# hello-ftdi-44.net
KiCad netlist of a schematic drawn in EAGLE
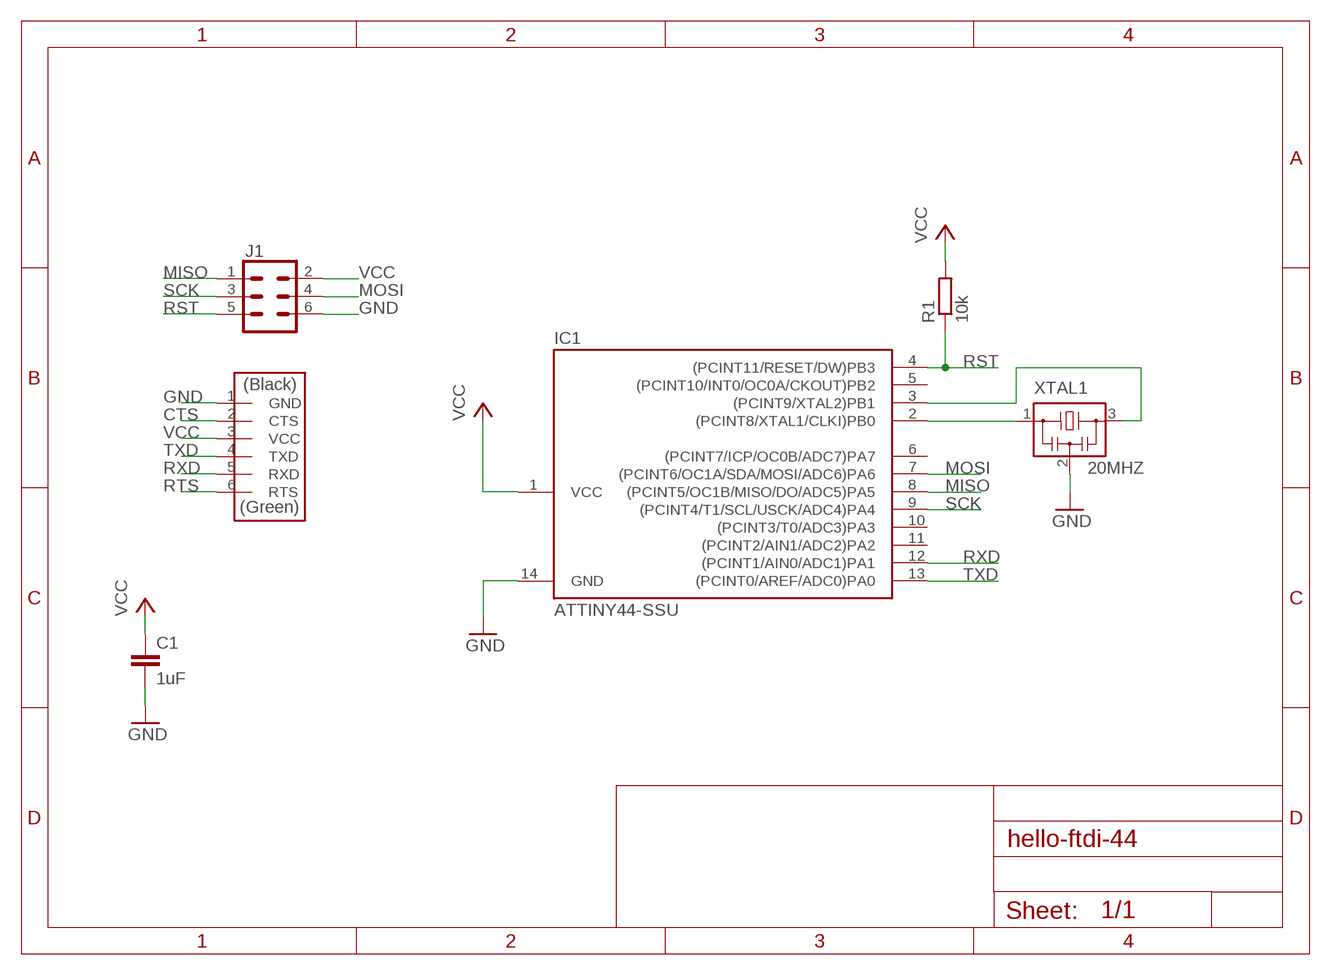
[diagram p0: schematic, sheet 1]

(export (version "E")
  (design (tool "Eeschema 10.0.6"))
  (components
    (comp (ref "C1")
      (value "1uF")
      (footprint "eagle-import:C1206")
      (libsource (lib "eagle-import") (part "C-EUC1206"))
    )
    (comp (ref "IC1")
      (value "ATTINY44-SSU")
      (footprint "eagle-import:SOIC14")
      (libsource (lib "eagle-import") (part "ATTINY44-SSU"))
    )
    (comp (ref "J1")
      (value "CONN_03X2SMT")
      (footprint "eagle-import:2X3_SMT_POSTS")
      (libsource (lib "eagle-import") (part "CONN_03X2SMT"))
    )
    (comp (ref "J2")
      (value "FTDI-SMD-HEADER")
      (footprint "eagle-import:1X06SMD")
      (libsource (lib "eagle-import") (part "FTDI-SMD-HEADER"))
    )
    (comp (ref "R1")
      (value "10k")
      (footprint "eagle-import:M1206")
      (libsource (lib "eagle-import") (part "R-EU_M1206"))
    )
    (comp (ref "XTAL1")
      (value "20MHZ")
      (footprint "eagle-import:EFOBM")
      (libsource (lib "eagle-import") (part "RESONATOR"))
    )
  )
  (nets
    (net (code "1") (name "/CTS") (class "Default")
      (node (ref "J2") (pin "2") (pinfunction "CTS_2") (pintype "bidirectional"))
    )
    (net (code "2") (name "/MISO") (class "Default")
      (node (ref "IC1") (pin "8") (pinfunction "(PCINT5/OC1B/MISO/DO/ADC5)PA5_8") (pintype "bidirectional"))
      (node (ref "J1") (pin "1") (pinfunction "1_1") (pintype "bidirectional"))
    )
    (net (code "3") (name "/MOSI") (class "Default")
      (node (ref "IC1") (pin "7") (pinfunction "(PCINT6/OC1A/SDA/MOSI/ADC6)PA6_7") (pintype "bidirectional"))
      (node (ref "J1") (pin "4") (pinfunction "4_4") (pintype "bidirectional"))
    )
    (net (code "4") (name "/RST") (class "Default")
      (node (ref "IC1") (pin "4") (pinfunction "(PCINT11/RESET/DW)PB3_4") (pintype "bidirectional"))
      (node (ref "J1") (pin "5") (pinfunction "5_5") (pintype "bidirectional"))
      (node (ref "R1") (pin "1") (pinfunction "1_1") (pintype "passive"))
    )
    (net (code "5") (name "/RTS") (class "Default")
      (node (ref "J2") (pin "6") (pinfunction "RTS_6") (pintype "bidirectional"))
    )
    (net (code "6") (name "/RXD") (class "Default")
      (node (ref "IC1") (pin "12") (pinfunction "(PCINT1/AIN0/ADC1)PA1_12") (pintype "bidirectional"))
      (node (ref "J2") (pin "5") (pinfunction "RXD_5") (pintype "bidirectional"))
    )
    (net (code "7") (name "/SCK") (class "Default")
      (node (ref "IC1") (pin "9") (pinfunction "(PCINT4/T1/SCL/USCK/ADC4)PA4_9") (pintype "bidirectional"))
      (node (ref "J1") (pin "3") (pinfunction "3_3") (pintype "bidirectional"))
    )
    (net (code "8") (name "/TXD") (class "Default")
      (node (ref "IC1") (pin "13") (pinfunction "(PCINT0/AREF/ADC0)PA0_13") (pintype "bidirectional"))
      (node (ref "J2") (pin "4") (pinfunction "TXD_4") (pintype "bidirectional"))
    )
    (net (code "9") (name "GND") (class "Default")
      (node (ref "C1") (pin "2") (pinfunction "2_2") (pintype "passive"))
      (node (ref "IC1") (pin "14") (pinfunction "GND_14") (pintype "power_in"))
      (node (ref "J1") (pin "6") (pinfunction "6_6") (pintype "bidirectional"))
      (node (ref "J2") (pin "1") (pinfunction "GND_1") (pintype "bidirectional"))
      (node (ref "XTAL1") (pin "2") (pinfunction "2_2") (pintype "passive"))
    )
    (net (code "10") (name "Net-(IC1-(PCINT8{slash}XTAL1{slash}CLKI)PB0)") (class "Default")
      (node (ref "IC1") (pin "2") (pinfunction "(PCINT8/XTAL1/CLKI)PB0_2") (pintype "bidirectional"))
      (node (ref "XTAL1") (pin "1") (pinfunction "1_1") (pintype "passive"))
    )
    (net (code "11") (name "Net-(IC1-(PCINT9{slash}XTAL2)PB1)") (class "Default")
      (node (ref "IC1") (pin "3") (pinfunction "(PCINT9/XTAL2)PB1_3") (pintype "bidirectional"))
      (node (ref "XTAL1") (pin "3") (pinfunction "3_3") (pintype "passive"))
    )
    (net (code "12") (name "VCC") (class "Default")
      (node (ref "C1") (pin "1") (pinfunction "1_1") (pintype "passive"))
      (node (ref "IC1") (pin "1") (pinfunction "VCC_1") (pintype "power_in"))
      (node (ref "J1") (pin "2") (pinfunction "2_2") (pintype "bidirectional"))
      (node (ref "J2") (pin "3") (pinfunction "VCC_3") (pintype "bidirectional"))
      (node (ref "R1") (pin "2") (pinfunction "2_2") (pintype "passive"))
    )
    (net (code "13") (name "unconnected-(IC1-(PCINT2{slash}AIN1{slash}ADC2)PA2-Pad11)") (class "Default")
      (node (ref "IC1") (pin "11") (pinfunction "(PCINT2/AIN1/ADC2)PA2_11") (pintype "bidirectional"))
    )
    (net (code "14") (name "unconnected-(IC1-(PCINT3{slash}T0{slash}ADC3)PA3-Pad10)") (class "Default")
      (node (ref "IC1") (pin "10") (pinfunction "(PCINT3/T0/ADC3)PA3_10") (pintype "bidirectional"))
    )
    (net (code "15") (name "unconnected-(IC1-(PCINT7{slash}ICP{slash}OC0B{slash}ADC7)PA7-Pad6)") (class "Default")
      (node (ref "IC1") (pin "6") (pinfunction "(PCINT7/ICP/OC0B/ADC7)PA7_6") (pintype "bidirectional"))
    )
    (net (code "16") (name "unconnected-(IC1-(PCINT10{slash}INT0{slash}OC0A{slash}CKOUT)PB2-Pad5)") (class "Default")
      (node (ref "IC1") (pin "5") (pinfunction "(PCINT10/INT0/OC0A/CKOUT)PB2_5") (pintype "bidirectional"))
    )
  )
)
